# Board.net
KiCad netlist of a schematic drawn in EAGLE
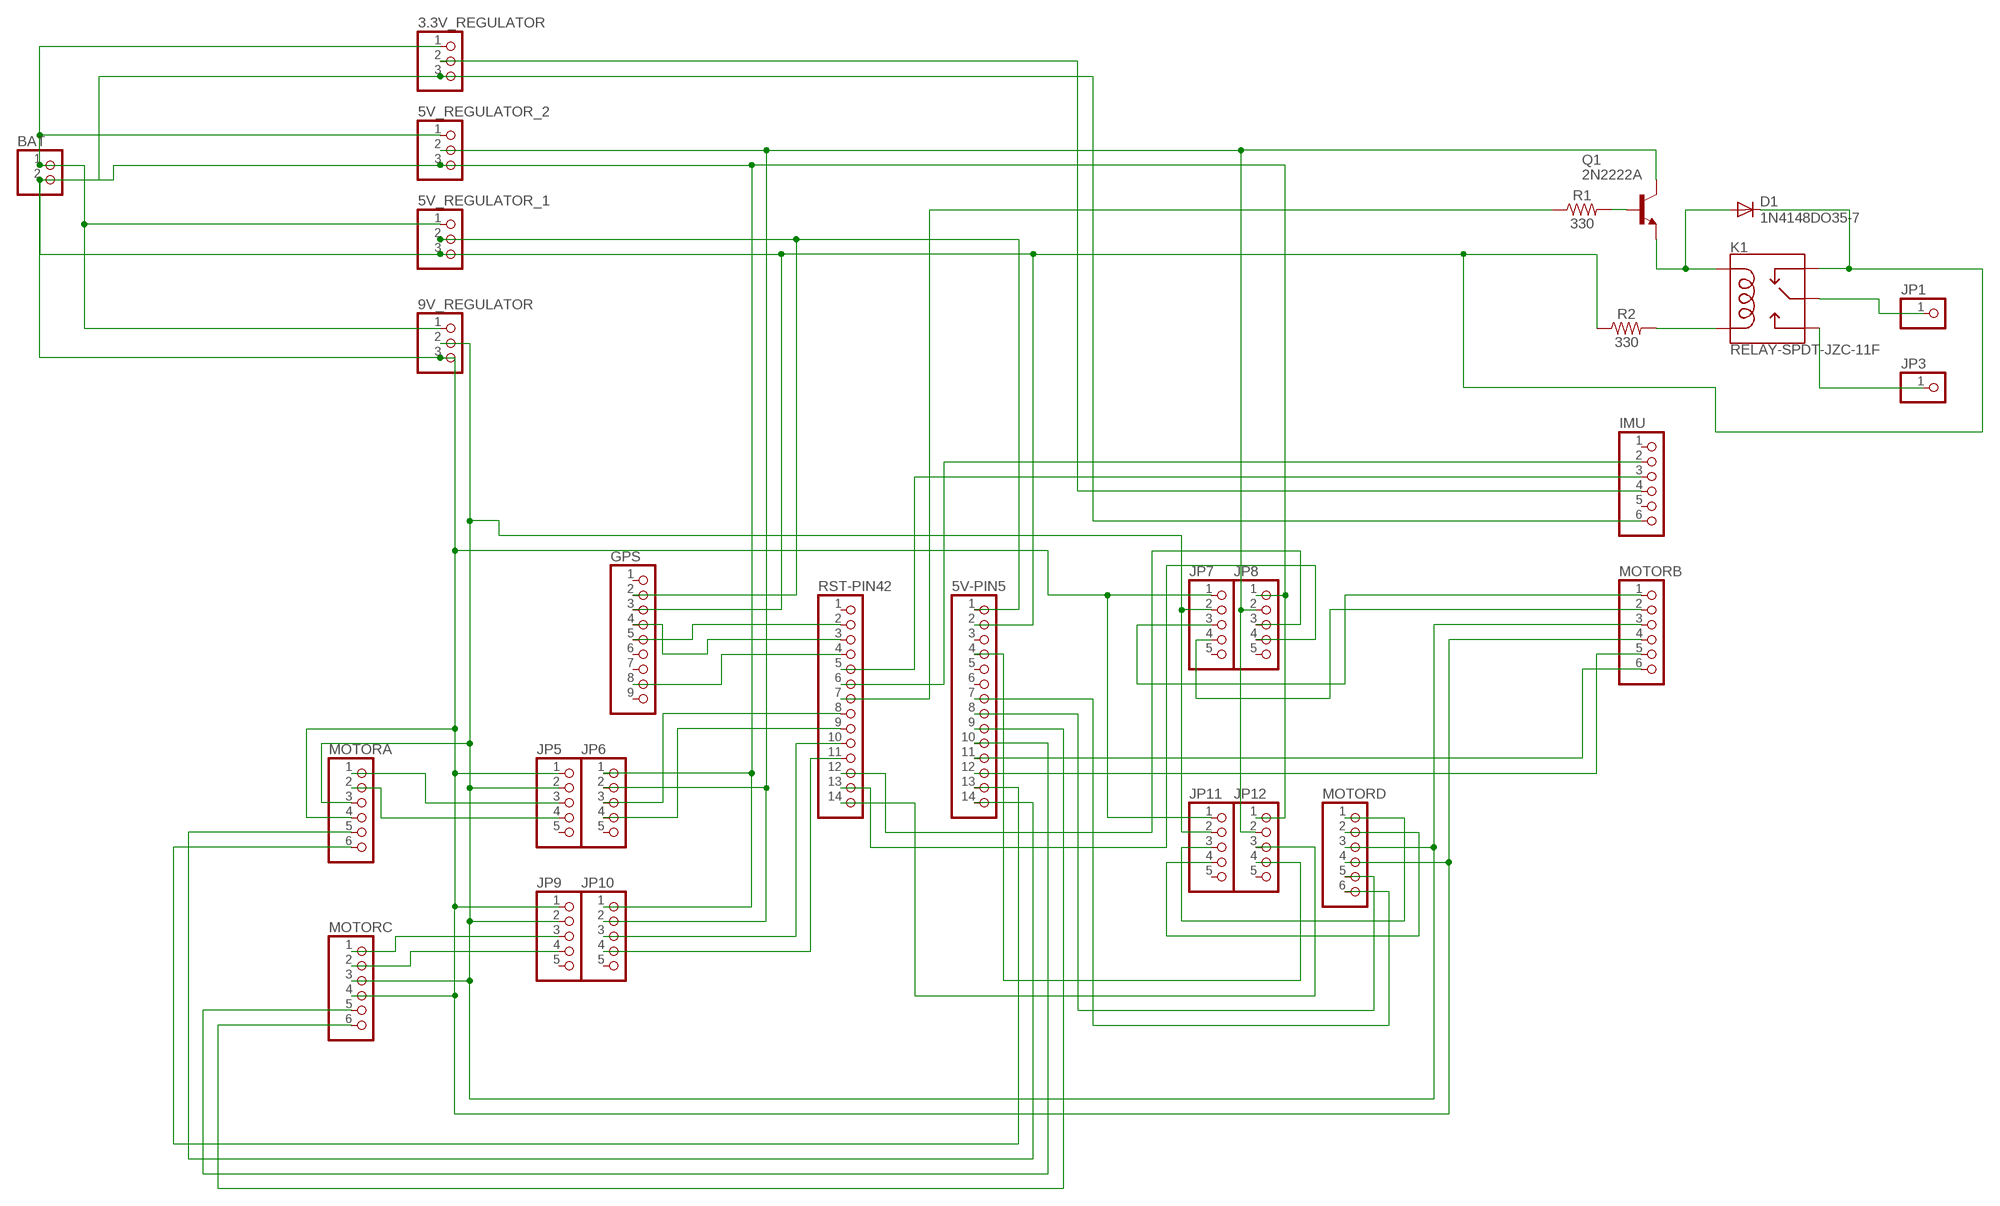
[diagram p0: schematic, sheet 1]

(export (version "E")
  (design (tool "Eeschema 10.0.6"))
  (components
    (comp (ref "3.3V_REGULATOR")
      (value "PINHD-1X3")
      (footprint "eagle-import:1X03")
      (libsource (lib "eagle-import") (part "PINHD-1X3"))
    )
    (comp (ref "5V-PIN5")
      (value "PINHD-1X14")
      (footprint "eagle-import:1X14")
      (libsource (lib "eagle-import") (part "PINHD-1X14"))
    )
    (comp (ref "5V_REGULATOR_1")
      (value "PINHD-1X3")
      (footprint "eagle-import:1X03")
      (libsource (lib "eagle-import") (part "PINHD-1X3"))
    )
    (comp (ref "5V_REGULATOR_2")
      (value "PINHD-1X3")
      (footprint "eagle-import:1X03")
      (libsource (lib "eagle-import") (part "PINHD-1X3"))
    )
    (comp (ref "9V_REGULATOR")
      (value "PINHD-1X3")
      (footprint "eagle-import:1X03")
      (libsource (lib "eagle-import") (part "PINHD-1X3"))
    )
    (comp (ref "BAT")
      (value "PINHD-1X2")
      (footprint "eagle-import:1X02")
      (libsource (lib "eagle-import") (part "PINHD-1X2"))
    )
    (comp (ref "D1")
      (value "1N4148DO35-7")
      (footprint "eagle-import:DO35-7")
      (libsource (lib "eagle-import") (part "1N4148DO35-7"))
    )
    (comp (ref "GPS")
      (value "PINHD-1X9")
      (footprint "eagle-import:1X09")
      (libsource (lib "eagle-import") (part "PINHD-1X9"))
    )
    (comp (ref "IMU")
      (value "PINHD-1X6")
      (footprint "eagle-import:1X06")
      (libsource (lib "eagle-import") (part "PINHD-1X6"))
    )
    (comp (ref "JP1")
      (value "PINHD-1X1")
      (footprint "eagle-import:1X01")
      (libsource (lib "eagle-import") (part "PINHD-1X1"))
    )
    (comp (ref "JP3")
      (value "PINHD-1X1")
      (footprint "eagle-import:1X01")
      (libsource (lib "eagle-import") (part "PINHD-1X1"))
    )
    (comp (ref "JP5")
      (value "PINHD-1X5")
      (footprint "eagle-import:1X05")
      (libsource (lib "eagle-import") (part "PINHD-1X5"))
    )
    (comp (ref "JP6")
      (value "PINHD-1X5")
      (footprint "eagle-import:1X05")
      (libsource (lib "eagle-import") (part "PINHD-1X5"))
    )
    (comp (ref "JP7")
      (value "PINHD-1X5")
      (footprint "eagle-import:1X05")
      (libsource (lib "eagle-import") (part "PINHD-1X5"))
    )
    (comp (ref "JP8")
      (value "PINHD-1X5")
      (footprint "eagle-import:1X05")
      (libsource (lib "eagle-import") (part "PINHD-1X5"))
    )
    (comp (ref "JP9")
      (value "PINHD-1X5")
      (footprint "eagle-import:1X05")
      (libsource (lib "eagle-import") (part "PINHD-1X5"))
    )
    (comp (ref "JP10")
      (value "PINHD-1X5")
      (footprint "eagle-import:1X05")
      (libsource (lib "eagle-import") (part "PINHD-1X5"))
    )
    (comp (ref "JP11")
      (value "PINHD-1X5")
      (footprint "eagle-import:1X05")
      (libsource (lib "eagle-import") (part "PINHD-1X5"))
    )
    (comp (ref "JP12")
      (value "PINHD-1X5")
      (footprint "eagle-import:1X05")
      (libsource (lib "eagle-import") (part "PINHD-1X5"))
    )
    (comp (ref "K1")
      (value "RELAY-SPDT-JZC-11F")
      (footprint "eagle-import:RELAY-JZC")
      (libsource (lib "eagle-import") (part "RELAY-SPDT-JZC-11F"))
    )
    (comp (ref "MOTORA")
      (value "PINHD-1X6")
      (footprint "eagle-import:1X06")
      (libsource (lib "eagle-import") (part "PINHD-1X6"))
    )
    (comp (ref "MOTORB")
      (value "PINHD-1X6")
      (footprint "eagle-import:1X06")
      (libsource (lib "eagle-import") (part "PINHD-1X6"))
    )
    (comp (ref "MOTORC")
      (value "PINHD-1X6")
      (footprint "eagle-import:1X06")
      (libsource (lib "eagle-import") (part "PINHD-1X6"))
    )
    (comp (ref "MOTORD")
      (value "PINHD-1X6")
      (footprint "eagle-import:1X06")
      (libsource (lib "eagle-import") (part "PINHD-1X6"))
    )
    (comp (ref "Q1")
      (value "2N2222A")
      (footprint "eagle-import:TO18")
      (libsource (lib "eagle-import") (part "2N2222A"))
    )
    (comp (ref "R1")
      (value "330")
      (footprint "eagle-import:0603")
      (libsource (lib "eagle-import") (part "330OHM-0603-1/10W-1%"))
    )
    (comp (ref "R2")
      (value "330")
      (footprint "eagle-import:0603")
      (libsource (lib "eagle-import") (part "330OHM-0603-1/10W-1%"))
    )
    (comp (ref "RST-PIN42")
      (value "PINHD-1X14")
      (footprint "eagle-import:1X14")
      (libsource (lib "eagle-import") (part "PINHD-1X14"))
    )
  )
  (nets
    (net (code "1") (name "Net-(3.3V_REGULATOR-Pad1)") (class "Default")
      (node (ref "3.3V_REGULATOR") (pin "1") (pinfunction "1_1") (pintype "passive"))
      (node (ref "5V_REGULATOR_1") (pin "1") (pinfunction "1_1") (pintype "passive"))
      (node (ref "5V_REGULATOR_2") (pin "1") (pinfunction "1_1") (pintype "passive"))
      (node (ref "9V_REGULATOR") (pin "1") (pinfunction "1_1") (pintype "passive"))
      (node (ref "BAT") (pin "1") (pinfunction "1_1") (pintype "passive"))
    )
    (net (code "2") (name "Net-(3.3V_REGULATOR-Pad2)") (class "Default")
      (node (ref "3.3V_REGULATOR") (pin "2") (pinfunction "2_2") (pintype "passive"))
      (node (ref "IMU") (pin "4") (pinfunction "4_4") (pintype "passive"))
    )
    (net (code "3") (name "Net-(5V-PIN5-Pad1)") (class "Default")
      (node (ref "5V-PIN5") (pin "1") (pinfunction "1_1") (pintype "passive"))
      (node (ref "5V_REGULATOR_1") (pin "2") (pinfunction "2_2") (pintype "passive"))
      (node (ref "GPS") (pin "2") (pinfunction "2_2") (pintype "passive"))
    )
    (net (code "4") (name "Net-(5V-PIN5-Pad4)") (class "Default")
      (node (ref "5V-PIN5") (pin "4") (pinfunction "4_4") (pintype "passive"))
      (node (ref "JP12") (pin "4") (pinfunction "4_4") (pintype "passive"))
    )
    (net (code "5") (name "Net-(5V-PIN5-Pad7)") (class "Default")
      (node (ref "5V-PIN5") (pin "7") (pinfunction "7_7") (pintype "passive"))
      (node (ref "MOTORD") (pin "6") (pinfunction "6_6") (pintype "passive"))
    )
    (net (code "6") (name "Net-(5V-PIN5-Pad8)") (class "Default")
      (node (ref "5V-PIN5") (pin "8") (pinfunction "8_8") (pintype "passive"))
      (node (ref "MOTORD") (pin "5") (pinfunction "5_5") (pintype "passive"))
    )
    (net (code "7") (name "Net-(5V-PIN5-Pad9)") (class "Default")
      (node (ref "5V-PIN5") (pin "9") (pinfunction "9_9") (pintype "passive"))
      (node (ref "MOTORC") (pin "6") (pinfunction "6_6") (pintype "passive"))
    )
    (net (code "8") (name "Net-(5V-PIN5-Pad10)") (class "Default")
      (node (ref "5V-PIN5") (pin "10") (pinfunction "10_10") (pintype "passive"))
      (node (ref "MOTORC") (pin "5") (pinfunction "5_5") (pintype "passive"))
    )
    (net (code "9") (name "Net-(5V-PIN5-Pad11)") (class "Default")
      (node (ref "5V-PIN5") (pin "11") (pinfunction "11_11") (pintype "passive"))
      (node (ref "MOTORB") (pin "6") (pinfunction "6_6") (pintype "passive"))
    )
    (net (code "10") (name "Net-(5V-PIN5-Pad12)") (class "Default")
      (node (ref "5V-PIN5") (pin "12") (pinfunction "12_12") (pintype "passive"))
      (node (ref "MOTORB") (pin "5") (pinfunction "5_5") (pintype "passive"))
    )
    (net (code "11") (name "Net-(5V-PIN5-Pad13)") (class "Default")
      (node (ref "5V-PIN5") (pin "13") (pinfunction "13_13") (pintype "passive"))
      (node (ref "MOTORA") (pin "6") (pinfunction "6_6") (pintype "passive"))
    )
    (net (code "12") (name "Net-(5V-PIN5-Pad14)") (class "Default")
      (node (ref "5V-PIN5") (pin "14") (pinfunction "14_14") (pintype "passive"))
      (node (ref "MOTORA") (pin "5") (pinfunction "5_5") (pintype "passive"))
    )
    (net (code "13") (name "Net-(9V_REGULATOR-Pad2)") (class "Default")
      (node (ref "9V_REGULATOR") (pin "2") (pinfunction "2_2") (pintype "passive"))
      (node (ref "JP11") (pin "2") (pinfunction "2_2") (pintype "passive"))
      (node (ref "JP5") (pin "2") (pinfunction "2_2") (pintype "passive"))
      (node (ref "JP7") (pin "2") (pinfunction "2_2") (pintype "passive"))
      (node (ref "JP9") (pin "2") (pinfunction "2_2") (pintype "passive"))
      (node (ref "MOTORA") (pin "3") (pinfunction "3_3") (pintype "passive"))
      (node (ref "MOTORB") (pin "3") (pinfunction "3_3") (pintype "passive"))
      (node (ref "MOTORC") (pin "3") (pinfunction "3_3") (pintype "passive"))
      (node (ref "MOTORD") (pin "3") (pinfunction "3_3") (pintype "passive"))
    )
    (net (code "14") (name "Net-(GPS-Pad4)") (class "Default")
      (node (ref "GPS") (pin "4") (pinfunction "4_4") (pintype "passive"))
      (node (ref "RST-PIN42") (pin "3") (pinfunction "3_3") (pintype "passive"))
    )
    (net (code "15") (name "Net-(GPS-Pad5)") (class "Default")
      (node (ref "GPS") (pin "5") (pinfunction "5_5") (pintype "passive"))
      (node (ref "RST-PIN42") (pin "2") (pinfunction "2_2") (pintype "passive"))
    )
    (net (code "16") (name "Net-(GPS-Pad8)") (class "Default")
      (node (ref "GPS") (pin "8") (pinfunction "8_8") (pintype "passive"))
      (node (ref "RST-PIN42") (pin "4") (pinfunction "4_4") (pintype "passive"))
    )
    (net (code "17") (name "Net-(IMU-Pad2)") (class "Default")
      (node (ref "IMU") (pin "2") (pinfunction "2_2") (pintype "passive"))
      (node (ref "RST-PIN42") (pin "6") (pinfunction "6_6") (pintype "passive"))
    )
    (net (code "18") (name "Net-(IMU-Pad3)") (class "Default")
      (node (ref "IMU") (pin "3") (pinfunction "3_3") (pintype "passive"))
      (node (ref "RST-PIN42") (pin "5") (pinfunction "5_5") (pintype "passive"))
    )
    (net (code "19") (name "Net-(JP5-Pad3)") (class "Default")
      (node (ref "JP5") (pin "3") (pinfunction "3_3") (pintype "passive"))
      (node (ref "MOTORA") (pin "1") (pinfunction "1_1") (pintype "passive"))
    )
    (net (code "20") (name "Net-(JP5-Pad4)") (class "Default")
      (node (ref "JP5") (pin "4") (pinfunction "4_4") (pintype "passive"))
      (node (ref "MOTORA") (pin "2") (pinfunction "2_2") (pintype "passive"))
    )
    (net (code "21") (name "Net-(JP6-Pad3)") (class "Default")
      (node (ref "JP6") (pin "3") (pinfunction "3_3") (pintype "passive"))
      (node (ref "RST-PIN42") (pin "8") (pinfunction "8_8") (pintype "passive"))
    )
    (net (code "22") (name "Net-(JP6-Pad4)") (class "Default")
      (node (ref "JP6") (pin "4") (pinfunction "4_4") (pintype "passive"))
      (node (ref "RST-PIN42") (pin "9") (pinfunction "9_9") (pintype "passive"))
    )
    (net (code "23") (name "Net-(JP7-Pad3)") (class "Default")
      (node (ref "JP7") (pin "3") (pinfunction "3_3") (pintype "passive"))
      (node (ref "MOTORB") (pin "1") (pinfunction "1_1") (pintype "passive"))
    )
    (net (code "24") (name "Net-(JP7-Pad4)") (class "Default")
      (node (ref "JP7") (pin "4") (pinfunction "4_4") (pintype "passive"))
      (node (ref "MOTORB") (pin "2") (pinfunction "2_2") (pintype "passive"))
    )
    (net (code "25") (name "Net-(JP8-Pad3)") (class "Default")
      (node (ref "JP8") (pin "3") (pinfunction "3_3") (pintype "passive"))
      (node (ref "RST-PIN42") (pin "12") (pinfunction "12_12") (pintype "passive"))
    )
    (net (code "26") (name "Net-(JP8-Pad4)") (class "Default")
      (node (ref "JP8") (pin "4") (pinfunction "4_4") (pintype "passive"))
      (node (ref "RST-PIN42") (pin "13") (pinfunction "13_13") (pintype "passive"))
    )
    (net (code "27") (name "Net-(JP9-Pad3)") (class "Default")
      (node (ref "JP9") (pin "3") (pinfunction "3_3") (pintype "passive"))
      (node (ref "MOTORC") (pin "1") (pinfunction "1_1") (pintype "passive"))
    )
    (net (code "28") (name "Net-(JP9-Pad4)") (class "Default")
      (node (ref "JP9") (pin "4") (pinfunction "4_4") (pintype "passive"))
      (node (ref "MOTORC") (pin "2") (pinfunction "2_2") (pintype "passive"))
    )
    (net (code "29") (name "Net-(JP10-Pad3)") (class "Default")
      (node (ref "JP10") (pin "3") (pinfunction "3_3") (pintype "passive"))
      (node (ref "RST-PIN42") (pin "10") (pinfunction "10_10") (pintype "passive"))
    )
    (net (code "30") (name "Net-(JP10-Pad4)") (class "Default")
      (node (ref "JP10") (pin "4") (pinfunction "4_4") (pintype "passive"))
      (node (ref "RST-PIN42") (pin "11") (pinfunction "11_11") (pintype "passive"))
    )
    (net (code "31") (name "Net-(JP11-Pad3)") (class "Default")
      (node (ref "JP11") (pin "3") (pinfunction "3_3") (pintype "passive"))
      (node (ref "MOTORD") (pin "1") (pinfunction "1_1") (pintype "passive"))
    )
    (net (code "32") (name "Net-(JP11-Pad4)") (class "Default")
      (node (ref "JP11") (pin "4") (pinfunction "4_4") (pintype "passive"))
      (node (ref "MOTORD") (pin "2") (pinfunction "2_2") (pintype "passive"))
    )
    (net (code "33") (name "Net-(JP12-Pad3)") (class "Default")
      (node (ref "JP12") (pin "3") (pinfunction "3_3") (pintype "passive"))
      (node (ref "RST-PIN42") (pin "14") (pinfunction "14_14") (pintype "passive"))
    )
    (net (code "34") (name "Net-(K1-COIL1)") (class "Default")
      (node (ref "D1") (pin "A") (pinfunction "A_A") (pintype "passive"))
      (node (ref "K1") (pin "5") (pinfunction "COIL1_5") (pintype "bidirectional"))
      (node (ref "Q1") (pin "1") (pinfunction "E_1") (pintype "passive"))
    )
    (net (code "35") (name "Net-(K1-COIL2)") (class "Default")
      (node (ref "K1") (pin "1") (pinfunction "COIL2_1") (pintype "bidirectional"))
      (node (ref "R2") (pin "2") (pinfunction "2_2") (pintype "passive"))
    )
    (net (code "36") (name "Net-(K1-MAIN)") (class "Default")
      (node (ref "JP1") (pin "1") (pinfunction "1_1") (pintype "passive"))
      (node (ref "K1") (pin "4") (pinfunction "MAIN_4") (pintype "bidirectional"))
    )
    (net (code "37") (name "Net-(K1-NC)") (class "Default")
      (node (ref "3.3V_REGULATOR") (pin "3") (pinfunction "3_3") (pintype "passive"))
      (node (ref "5V-PIN5") (pin "2") (pinfunction "2_2") (pintype "passive"))
      (node (ref "5V_REGULATOR_1") (pin "3") (pinfunction "3_3") (pintype "passive"))
      (node (ref "5V_REGULATOR_2") (pin "3") (pinfunction "3_3") (pintype "passive"))
      (node (ref "9V_REGULATOR") (pin "3") (pinfunction "3_3") (pintype "passive"))
      (node (ref "BAT") (pin "2") (pinfunction "2_2") (pintype "passive"))
      (node (ref "D1") (pin "C") (pinfunction "C_C") (pintype "passive"))
      (node (ref "GPS") (pin "3") (pinfunction "3_3") (pintype "passive"))
      (node (ref "IMU") (pin "6") (pinfunction "6_6") (pintype "passive"))
      (node (ref "JP10") (pin "1") (pinfunction "1_1") (pintype "passive"))
      (node (ref "JP11") (pin "1") (pinfunction "1_1") (pintype "passive"))
      (node (ref "JP12") (pin "1") (pinfunction "1_1") (pintype "passive"))
      (node (ref "JP5") (pin "1") (pinfunction "1_1") (pintype "passive"))
      (node (ref "JP6") (pin "1") (pinfunction "1_1") (pintype "passive"))
      (node (ref "JP7") (pin "1") (pinfunction "1_1") (pintype "passive"))
      (node (ref "JP8") (pin "1") (pinfunction "1_1") (pintype "passive"))
      (node (ref "JP9") (pin "1") (pinfunction "1_1") (pintype "passive"))
      (node (ref "K1") (pin "2") (pinfunction "NC_2") (pintype "bidirectional"))
      (node (ref "MOTORA") (pin "4") (pinfunction "4_4") (pintype "passive"))
      (node (ref "MOTORB") (pin "4") (pinfunction "4_4") (pintype "passive"))
      (node (ref "MOTORC") (pin "4") (pinfunction "4_4") (pintype "passive"))
      (node (ref "MOTORD") (pin "4") (pinfunction "4_4") (pintype "passive"))
      (node (ref "R2") (pin "1") (pinfunction "1_1") (pintype "passive"))
    )
    (net (code "38") (name "Net-(K1-NO)") (class "Default")
      (node (ref "JP3") (pin "1") (pinfunction "1_1") (pintype "passive"))
      (node (ref "K1") (pin "3") (pinfunction "NO_3") (pintype "bidirectional"))
    )
    (net (code "39") (name "Net-(Q1-B)") (class "Default")
      (node (ref "Q1") (pin "2") (pinfunction "B_2") (pintype "passive"))
      (node (ref "R1") (pin "2") (pinfunction "2_2") (pintype "passive"))
    )
    (net (code "40") (name "Net-(Q1-C)") (class "Default")
      (node (ref "5V_REGULATOR_2") (pin "2") (pinfunction "2_2") (pintype "passive"))
      (node (ref "JP10") (pin "2") (pinfunction "2_2") (pintype "passive"))
      (node (ref "JP12") (pin "2") (pinfunction "2_2") (pintype "passive"))
      (node (ref "JP6") (pin "2") (pinfunction "2_2") (pintype "passive"))
      (node (ref "JP8") (pin "2") (pinfunction "2_2") (pintype "passive"))
      (node (ref "Q1") (pin "3") (pinfunction "C_3") (pintype "passive"))
    )
    (net (code "41") (name "Net-(R1-Pad1)") (class "Default")
      (node (ref "R1") (pin "1") (pinfunction "1_1") (pintype "passive"))
      (node (ref "RST-PIN42") (pin "7") (pinfunction "7_7") (pintype "passive"))
    )
    (net (code "42") (name "unconnected-(5V-PIN5-Pad3)") (class "Default")
      (node (ref "5V-PIN5") (pin "3") (pinfunction "3_3") (pintype "passive"))
    )
    (net (code "43") (name "unconnected-(5V-PIN5-Pad5)") (class "Default")
      (node (ref "5V-PIN5") (pin "5") (pinfunction "5_5") (pintype "passive"))
    )
    (net (code "44") (name "unconnected-(5V-PIN5-Pad6)") (class "Default")
      (node (ref "5V-PIN5") (pin "6") (pinfunction "6_6") (pintype "passive"))
    )
    (net (code "45") (name "unconnected-(GPS-Pad1)") (class "Default")
      (node (ref "GPS") (pin "1") (pinfunction "1_1") (pintype "passive"))
    )
    (net (code "46") (name "unconnected-(GPS-Pad6)") (class "Default")
      (node (ref "GPS") (pin "6") (pinfunction "6_6") (pintype "passive"))
    )
    (net (code "47") (name "unconnected-(GPS-Pad7)") (class "Default")
      (node (ref "GPS") (pin "7") (pinfunction "7_7") (pintype "passive"))
    )
    (net (code "48") (name "unconnected-(GPS-Pad9)") (class "Default")
      (node (ref "GPS") (pin "9") (pinfunction "9_9") (pintype "passive"))
    )
    (net (code "49") (name "unconnected-(IMU-Pad1)") (class "Default")
      (node (ref "IMU") (pin "1") (pinfunction "1_1") (pintype "passive"))
    )
    (net (code "50") (name "unconnected-(IMU-Pad5)") (class "Default")
      (node (ref "IMU") (pin "5") (pinfunction "5_5") (pintype "passive"))
    )
    (net (code "51") (name "unconnected-(JP5-Pad5)") (class "Default")
      (node (ref "JP5") (pin "5") (pinfunction "5_5") (pintype "passive"))
    )
    (net (code "52") (name "unconnected-(JP6-Pad5)") (class "Default")
      (node (ref "JP6") (pin "5") (pinfunction "5_5") (pintype "passive"))
    )
    (net (code "53") (name "unconnected-(JP7-Pad5)") (class "Default")
      (node (ref "JP7") (pin "5") (pinfunction "5_5") (pintype "passive"))
    )
    (net (code "54") (name "unconnected-(JP8-Pad5)") (class "Default")
      (node (ref "JP8") (pin "5") (pinfunction "5_5") (pintype "passive"))
    )
    (net (code "55") (name "unconnected-(JP9-Pad5)") (class "Default")
      (node (ref "JP9") (pin "5") (pinfunction "5_5") (pintype "passive"))
    )
    (net (code "56") (name "unconnected-(JP10-Pad5)") (class "Default")
      (node (ref "JP10") (pin "5") (pinfunction "5_5") (pintype "passive"))
    )
    (net (code "57") (name "unconnected-(JP11-Pad5)") (class "Default")
      (node (ref "JP11") (pin "5") (pinfunction "5_5") (pintype "passive"))
    )
    (net (code "58") (name "unconnected-(JP12-Pad5)") (class "Default")
      (node (ref "JP12") (pin "5") (pinfunction "5_5") (pintype "passive"))
    )
    (net (code "59") (name "unconnected-(RST-PIN42-Pad1)") (class "Default")
      (node (ref "RST-PIN42") (pin "1") (pinfunction "1_1") (pintype "passive"))
    )
  )
)
